# preamp_transistor.net
KiCad netlist of a schematic drawn in EasyEDA
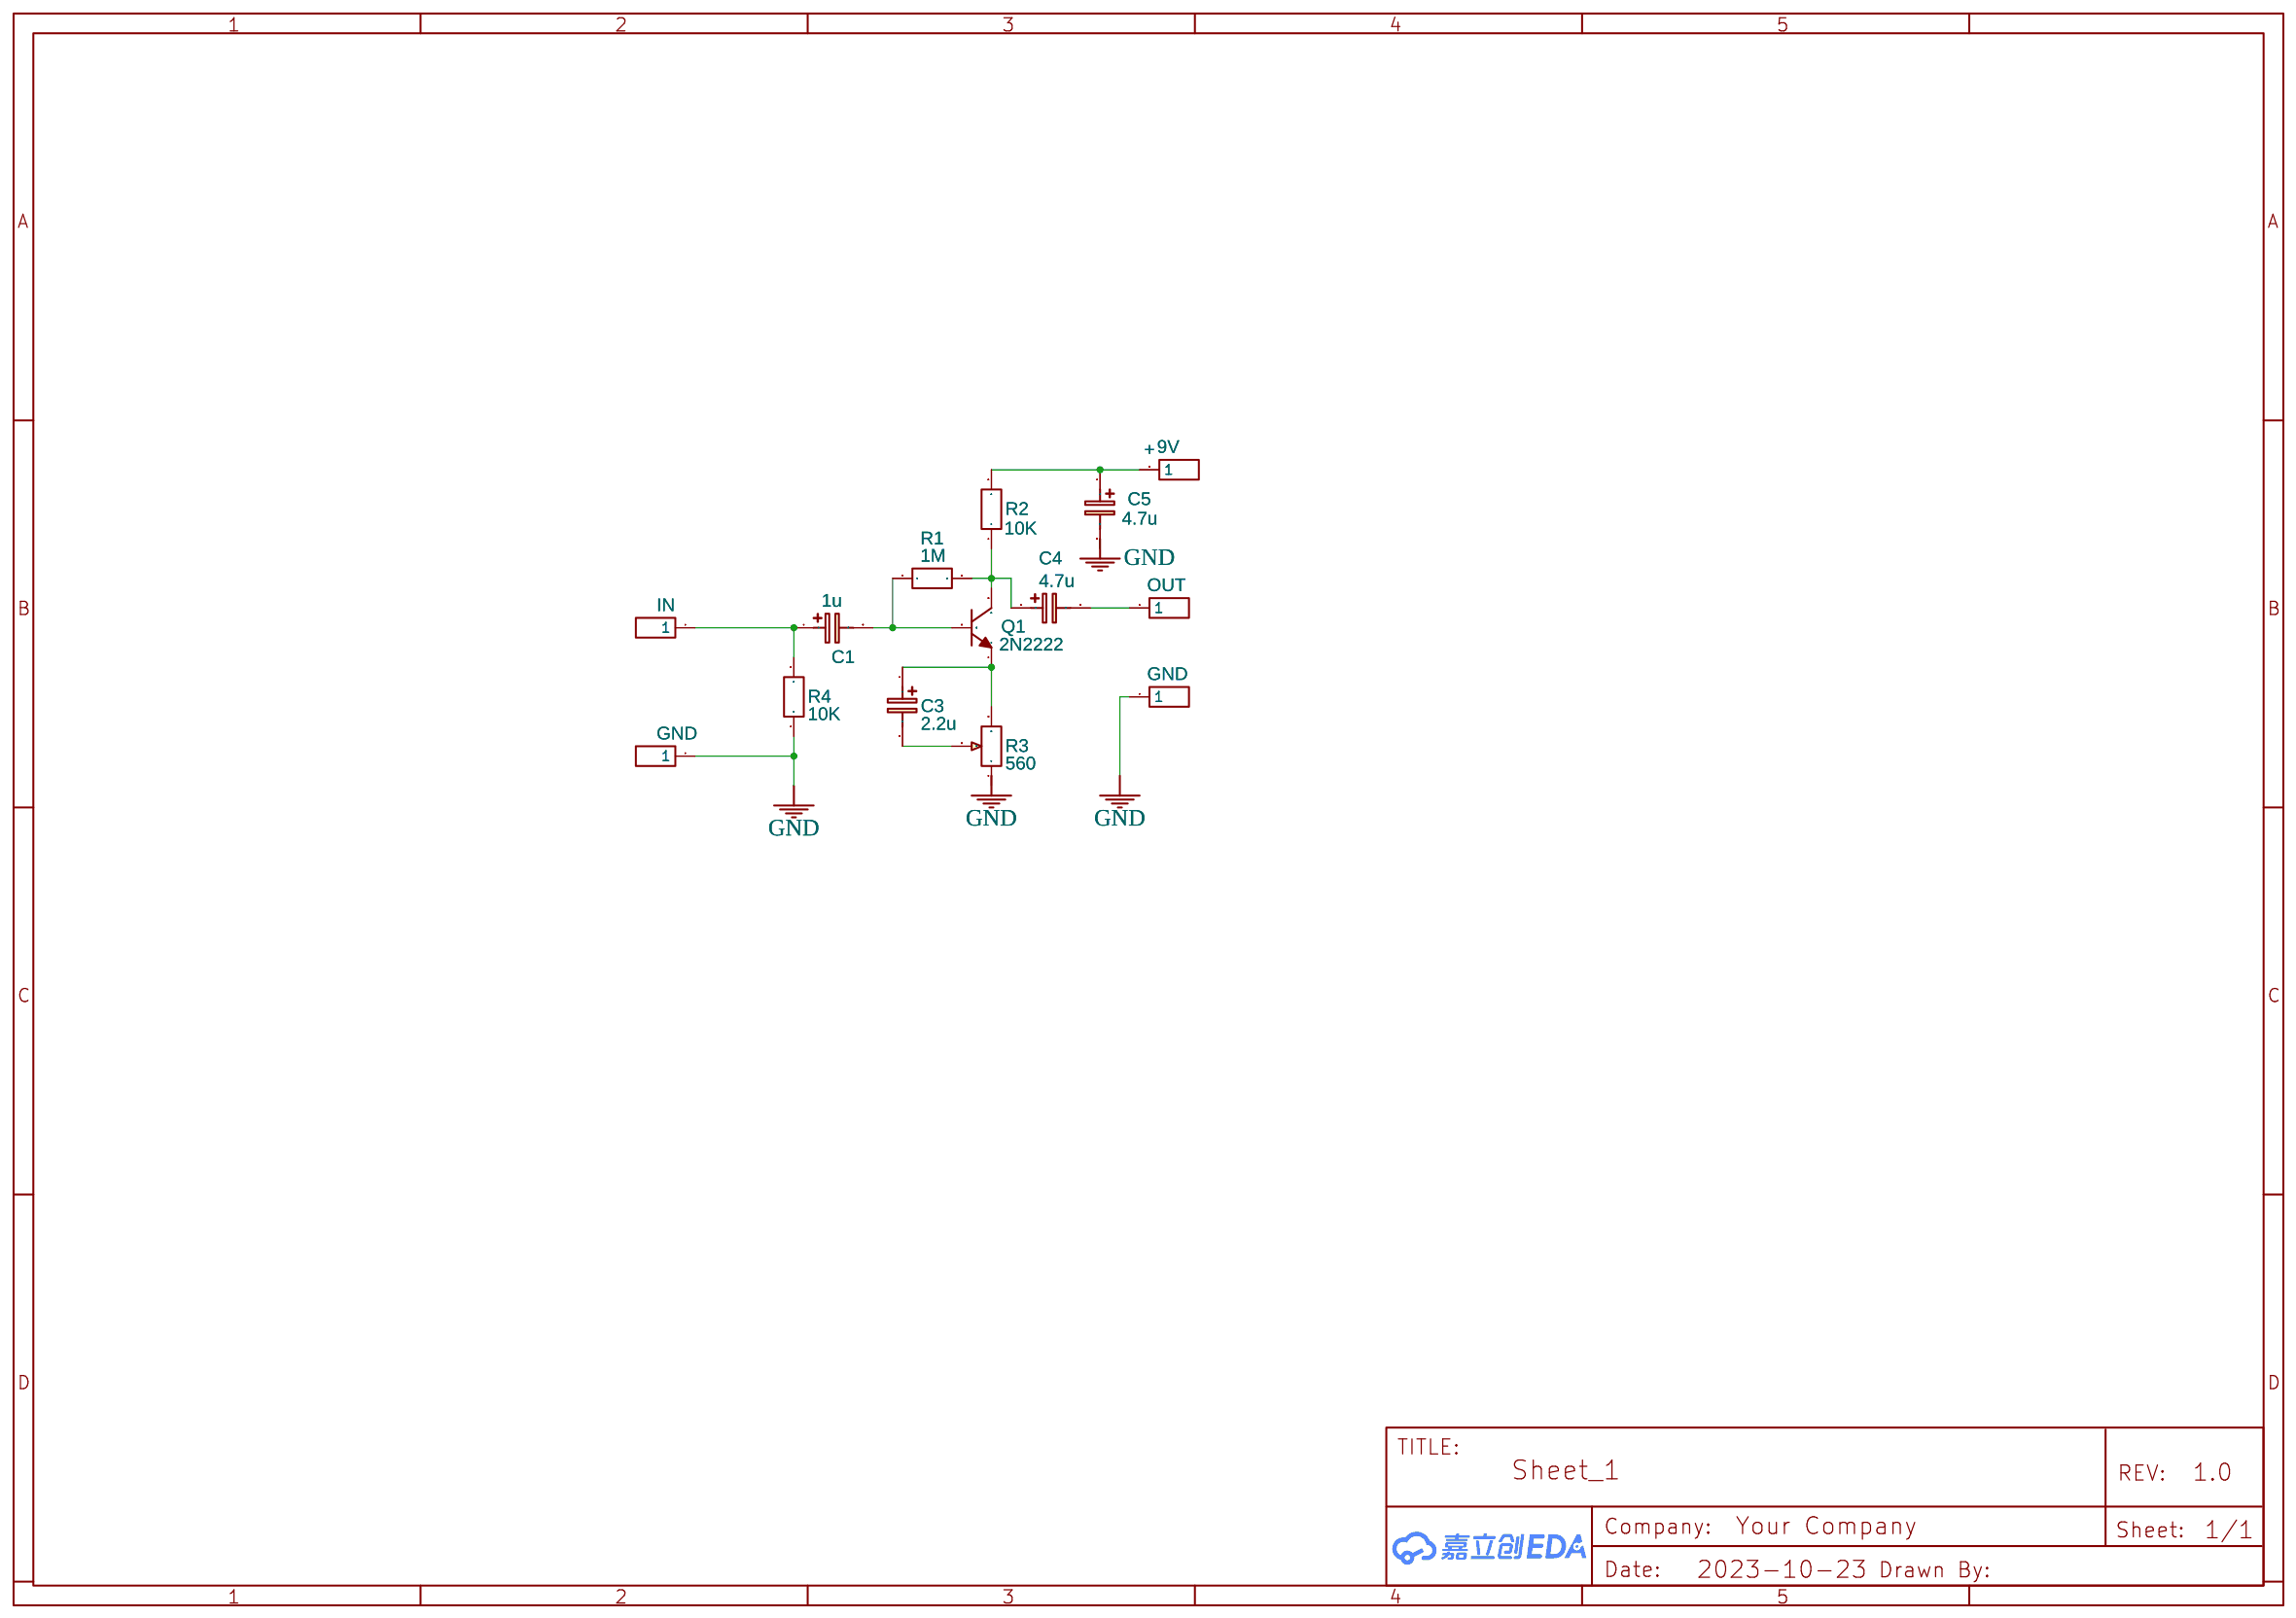
[diagram p0: schematic sheet]

(export (version "E")
  (design (tool "Eeschema 10.0.6"))
  (components
    (comp (ref "+")
      (value "9V")
      (fields (field (name "BOM_Supplier Part") "C81276"))
      (libsource (lib "") (part "HDR-M-2.54_1x1_2"))
    )
    (comp (ref "-")
      (value "GND")
      (fields (field (name "BOM_Supplier Part") "C81276"))
      (libsource (lib "") (part "HDR-M-2.54_1x1_3"))
    )
    (comp (ref "C1") (value "1u") (libsource (lib "") (part "C_Tan_SMD_A_EU_2")))
    (comp (ref "C3") (value "2.2u") (libsource (lib "") (part "C_Tan_SMD_A_EU_3")))
    (comp (ref "C4") (value "4.7u") (libsource (lib "") (part "C_Tan_SMD_A_EU")))
    (comp (ref "C5") (value "4.7u") (libsource (lib "") (part "C_Tan_SMD_A_EU_1")))
    (comp (ref "IGND")
      (value "GND")
      (fields (field (name "BOM_Supplier Part") "C81276"))
      (libsource (lib "") (part "HDR-M-2.54_1x1_4"))
    )
    (comp (ref "IN")
      (value "IN")
      (fields (field (name "BOM_Supplier Part") "C81276"))
      (libsource (lib "") (part "HDR-M-2.54_1x1"))
    )
    (comp (ref "OUT")
      (value "OUT")
      (fields (field (name "BOM_Supplier Part") "C81276"))
      (libsource (lib "") (part "HDR-M-2.54_1x1_1"))
    )
    (comp (ref "Q1")
      (value "2N2222")
      (fields
        (field (name "BOM_Manufacturer Part") "2n3904S-RTK/PS")
        (field (name "BOM_Supplier Part") "C18536")
      )
      (libsource (lib "") (part "2N3904(SOT-23)"))
    )
    (comp (ref "R1") (value "1M") (libsource (lib "") (part "R_0603_EU")))
    (comp (ref "R2") (value "10K") (libsource (lib "") (part "R_0603_EU_1")))
    (comp (ref "R3")
      (value "560")
      (fields (field (name "Manufacturer Part") "RM063-103 10K") (field (name "Manufacturer") "JML"))
      (libsource (lib "") (part "RM063-103 10K"))
    )
    (comp (ref "R4") (value "10K") (libsource (lib "") (part "R_0603_EU_1")))
  )
  (nets
    (net (code "1") (name "GND") (class "Default")
      (node (ref "-") (pin "1") (pinfunction "1_1") (pintype "input"))
      (node (ref "C5") (pin "2") (pinfunction "2_2") (pintype "unspecified"))
      (node (ref "IGND") (pin "1") (pinfunction "1_1") (pintype "input"))
      (node (ref "R3") (pin "1") (pinfunction "1_1") (pintype "input"))
      (node (ref "R4") (pin "1") (pinfunction "1_1") (pintype "unspecified"))
    )
    (net (code "2") (name "Net-(+-Pad1)") (class "Default")
      (node (ref "+") (pin "1") (pinfunction "1_1") (pintype "input"))
      (node (ref "C5") (pin "1") (pinfunction "1_1") (pintype "unspecified"))
      (node (ref "R2") (pin "2") (pinfunction "2_2") (pintype "unspecified"))
    )
    (net (code "3") (name "Net-(C1-Pad1)") (class "Default")
      (node (ref "C1") (pin "1") (pinfunction "1_1") (pintype "unspecified"))
      (node (ref "IN") (pin "1") (pinfunction "1_1") (pintype "input"))
      (node (ref "R4") (pin "2") (pinfunction "2_2") (pintype "unspecified"))
    )
    (net (code "4") (name "Net-(C3-Pad2)") (class "Default")
      (node (ref "C3") (pin "2") (pinfunction "2_2") (pintype "unspecified"))
      (node (ref "R3") (pin "2") (pinfunction "2_2") (pintype "input"))
    )
    (net (code "5") (name "Net-(C4-Pad2)") (class "Default")
      (node (ref "C4") (pin "2") (pinfunction "2_2") (pintype "unspecified"))
      (node (ref "OUT") (pin "1") (pinfunction "1_1") (pintype "input"))
    )
    (net (code "6") (name "Net-(Q1-B)") (class "Default")
      (node (ref "C1") (pin "2") (pinfunction "2_2") (pintype "unspecified"))
      (node (ref "Q1") (pin "2") (pinfunction "B_2") (pintype "input"))
      (node (ref "R1") (pin "1") (pinfunction "1_1") (pintype "unspecified"))
    )
    (net (code "7") (name "Net-(Q1-C)") (class "Default")
      (node (ref "C4") (pin "1") (pinfunction "1_1") (pintype "unspecified"))
      (node (ref "Q1") (pin "3") (pinfunction "C_3") (pintype "input"))
      (node (ref "R1") (pin "2") (pinfunction "2_2") (pintype "unspecified"))
      (node (ref "R2") (pin "1") (pinfunction "1_1") (pintype "unspecified"))
    )
    (net (code "8") (name "Net-(Q1-E)") (class "Default")
      (node (ref "C3") (pin "1") (pinfunction "1_1") (pintype "unspecified"))
      (node (ref "Q1") (pin "1") (pinfunction "E_1") (pintype "input"))
      (node (ref "R3") (pin "3") (pinfunction "3_3") (pintype "input"))
    )
  )
)
